# rpi2_relay2.net
KiCad netlist of a schematic drawn in EAGLE
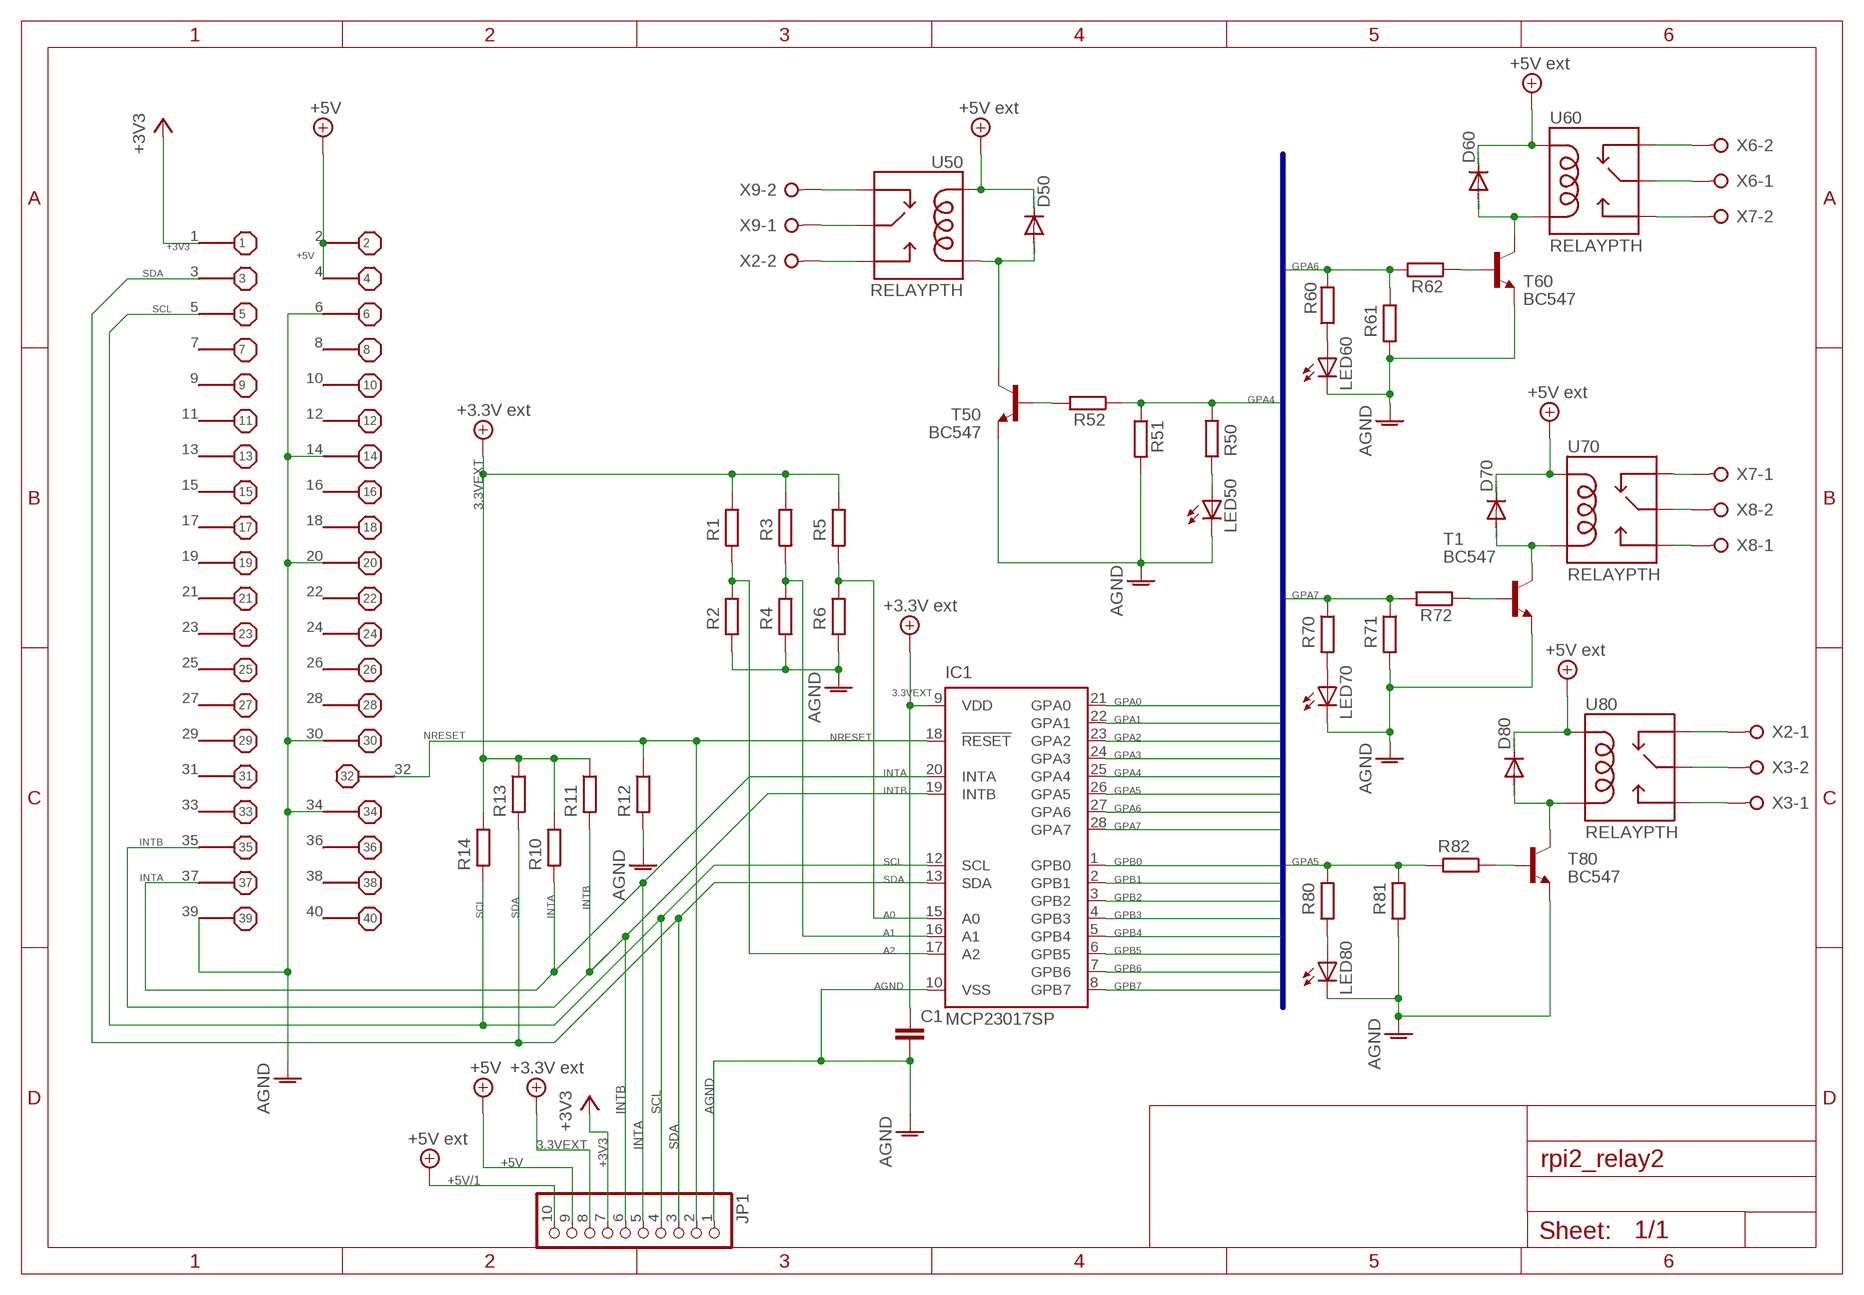
[diagram p0: schematic, sheet 1]

(export (version "E")
  (design (tool "Eeschema 10.0.6"))
  (components
    (comp (ref "C1")
      (value "C-EUC1210")
      (footprint "eagle-import:C1210")
      (libsource (lib "eagle-import") (part "C-EUC1210"))
    )
    (comp (ref "D50")
      (value "1N4148DO35-7")
      (footprint "eagle-import:DO35-7")
      (libsource (lib "eagle-import") (part "1N4148DO35-7"))
    )
    (comp (ref "D60")
      (value "1N4148DO35-7")
      (footprint "eagle-import:DO35-7")
      (libsource (lib "eagle-import") (part "1N4148DO35-7"))
    )
    (comp (ref "D70")
      (value "1N4148DO35-7")
      (footprint "eagle-import:DO35-7")
      (libsource (lib "eagle-import") (part "1N4148DO35-7"))
    )
    (comp (ref "D80")
      (value "1N4148DO35-7")
      (footprint "eagle-import:DO35-7")
      (libsource (lib "eagle-import") (part "1N4148DO35-7"))
    )
    (comp (ref "IC1")
      (value "MCP23017SP")
      (footprint "eagle-import:DIL28-3")
      (fields (field (name "MF") "MICROCHIP") (field (name "MPN") "MCP23017-E/SP"))
      (libsource (lib "eagle-import") (part "MCP23017SP"))
    )
    (comp (ref "JP1")
      (value "PINHD-1X10")
      (footprint "eagle-import:1X10")
      (libsource (lib "eagle-import") (part "PINHD-1X10"))
    )
    (comp (ref "LED50")
      (value "LEDCHIP-LED0805")
      (footprint "eagle-import:CHIP-LED0805")
      (libsource (lib "eagle-import") (part "LEDCHIP-LED0805"))
    )
    (comp (ref "LED60")
      (value "LEDCHIP-LED0805")
      (footprint "eagle-import:CHIP-LED0805")
      (libsource (lib "eagle-import") (part "LEDCHIP-LED0805"))
    )
    (comp (ref "LED70")
      (value "LEDCHIP-LED0805")
      (footprint "eagle-import:CHIP-LED0805")
      (libsource (lib "eagle-import") (part "LEDCHIP-LED0805"))
    )
    (comp (ref "LED80")
      (value "LEDCHIP-LED0805")
      (footprint "eagle-import:CHIP-LED0805")
      (libsource (lib "eagle-import") (part "LEDCHIP-LED0805"))
    )
    (comp (ref "R1")
      (value "R-EU_R0805")
      (footprint "eagle-import:R0805")
      (libsource (lib "eagle-import") (part "R-EU_R0805"))
    )
    (comp (ref "R2")
      (value "R-EU_R0805")
      (footprint "eagle-import:R0805")
      (libsource (lib "eagle-import") (part "R-EU_R0805"))
    )
    (comp (ref "R3")
      (value "R-EU_R0805")
      (footprint "eagle-import:R0805")
      (libsource (lib "eagle-import") (part "R-EU_R0805"))
    )
    (comp (ref "R4")
      (value "R-EU_R0805")
      (footprint "eagle-import:R0805")
      (libsource (lib "eagle-import") (part "R-EU_R0805"))
    )
    (comp (ref "R5")
      (value "R-EU_R0805")
      (footprint "eagle-import:R0805")
      (libsource (lib "eagle-import") (part "R-EU_R0805"))
    )
    (comp (ref "R6")
      (value "R-EU_R0805")
      (footprint "eagle-import:R0805")
      (libsource (lib "eagle-import") (part "R-EU_R0805"))
    )
    (comp (ref "R10")
      (value "R-EU_R0805")
      (footprint "eagle-import:R0805")
      (libsource (lib "eagle-import") (part "R-EU_R0805"))
    )
    (comp (ref "R11")
      (value "R-EU_R0805")
      (footprint "eagle-import:R0805")
      (libsource (lib "eagle-import") (part "R-EU_R0805"))
    )
    (comp (ref "R12")
      (value "R-EU_R0805")
      (footprint "eagle-import:R0805")
      (libsource (lib "eagle-import") (part "R-EU_R0805"))
    )
    (comp (ref "R13")
      (value "R-EU_R0805")
      (footprint "eagle-import:R0805")
      (libsource (lib "eagle-import") (part "R-EU_R0805"))
    )
    (comp (ref "R14")
      (value "R-EU_R0805")
      (footprint "eagle-import:R0805")
      (libsource (lib "eagle-import") (part "R-EU_R0805"))
    )
    (comp (ref "R50")
      (value "R-EU_R0805")
      (footprint "eagle-import:R0805")
      (libsource (lib "eagle-import") (part "R-EU_R0805"))
    )
    (comp (ref "R51")
      (value "R-EU_R0805")
      (footprint "eagle-import:R0805")
      (libsource (lib "eagle-import") (part "R-EU_R0805"))
    )
    (comp (ref "R52")
      (value "R-EU_R0805")
      (footprint "eagle-import:R0805")
      (libsource (lib "eagle-import") (part "R-EU_R0805"))
    )
    (comp (ref "R60")
      (value "R-EU_R0805")
      (footprint "eagle-import:R0805")
      (libsource (lib "eagle-import") (part "R-EU_R0805"))
    )
    (comp (ref "R61")
      (value "R-EU_R0805")
      (footprint "eagle-import:R0805")
      (libsource (lib "eagle-import") (part "R-EU_R0805"))
    )
    (comp (ref "R62")
      (value "R-EU_R0805")
      (footprint "eagle-import:R0805")
      (libsource (lib "eagle-import") (part "R-EU_R0805"))
    )
    (comp (ref "R70")
      (value "R-EU_R0805")
      (footprint "eagle-import:R0805")
      (libsource (lib "eagle-import") (part "R-EU_R0805"))
    )
    (comp (ref "R71")
      (value "R-EU_R0805")
      (footprint "eagle-import:R0805")
      (libsource (lib "eagle-import") (part "R-EU_R0805"))
    )
    (comp (ref "R72")
      (value "R-EU_R0805")
      (footprint "eagle-import:R0805")
      (libsource (lib "eagle-import") (part "R-EU_R0805"))
    )
    (comp (ref "R80")
      (value "R-EU_R0805")
      (footprint "eagle-import:R0805")
      (libsource (lib "eagle-import") (part "R-EU_R0805"))
    )
    (comp (ref "R81")
      (value "R-EU_R0805")
      (footprint "eagle-import:R0805")
      (libsource (lib "eagle-import") (part "R-EU_R0805"))
    )
    (comp (ref "R82")
      (value "R-EU_R0805")
      (footprint "eagle-import:R0805")
      (libsource (lib "eagle-import") (part "R-EU_R0805"))
    )
    (comp (ref "T1")
      (value "BC547")
      (footprint "eagle-import:TO92")
      (libsource (lib "eagle-import") (part "BC547"))
    )
    (comp (ref "T50")
      (value "BC547")
      (footprint "eagle-import:TO92")
      (libsource (lib "eagle-import") (part "BC547"))
    )
    (comp (ref "T60")
      (value "BC547")
      (footprint "eagle-import:TO92")
      (libsource (lib "eagle-import") (part "BC547"))
    )
    (comp (ref "T80")
      (value "BC547")
      (footprint "eagle-import:TO92")
      (libsource (lib "eagle-import") (part "BC547"))
    )
    (comp (ref "U50")
      (value "RELAYPTH")
      (footprint "eagle-import:SRD-05VDC-SL-C")
      (libsource (lib "eagle-import") (part "RELAYPTH"))
    )
    (comp (ref "U60")
      (value "RELAYPTH")
      (footprint "eagle-import:SRD-05VDC-SL-C")
      (libsource (lib "eagle-import") (part "RELAYPTH"))
    )
    (comp (ref "U70")
      (value "RELAYPTH")
      (footprint "eagle-import:SRD-05VDC-SL-C")
      (libsource (lib "eagle-import") (part "RELAYPTH"))
    )
    (comp (ref "U80")
      (value "RELAYPTH")
      (footprint "eagle-import:SRD-05VDC-SL-C")
      (libsource (lib "eagle-import") (part "RELAYPTH"))
    )
    (comp (ref "X1")
      (value "B+_GPIO")
      (footprint "eagle-import:B+_GPIO")
      (libsource (lib "eagle-import") (part "B+_GPIO"))
    )
    (comp (ref "X2")
      (value "W237-02P")
      (footprint "eagle-import:W237-132")
      (libsource (lib "eagle-import") (part "W237-02P"))
    )
    (comp (ref "X3")
      (value "W237-02P")
      (footprint "eagle-import:W237-132")
      (libsource (lib "eagle-import") (part "W237-02P"))
    )
    (comp (ref "X6")
      (value "W237-02P")
      (footprint "eagle-import:W237-132")
      (libsource (lib "eagle-import") (part "W237-02P"))
    )
    (comp (ref "X7")
      (value "W237-02P")
      (footprint "eagle-import:W237-132")
      (libsource (lib "eagle-import") (part "W237-02P"))
    )
    (comp (ref "X8")
      (value "W237-02P")
      (footprint "eagle-import:W237-132")
      (libsource (lib "eagle-import") (part "W237-02P"))
    )
    (comp (ref "X9")
      (value "W237-02P")
      (footprint "eagle-import:W237-132")
      (libsource (lib "eagle-import") (part "W237-02P"))
    )
  )
  (nets
    (net (code "1") (name "+3.3V ext") (class "Default")
      (node (ref "C1") (pin "1") (pinfunction "1_1") (pintype "passive"))
      (node (ref "IC1") (pin "9") (pinfunction "VDD_9") (pintype "power_in"))
      (node (ref "JP1") (pin "8") (pinfunction "8_8") (pintype "passive"))
      (node (ref "R1") (pin "1") (pinfunction "1_1") (pintype "passive"))
      (node (ref "R10") (pin "1") (pinfunction "1_1") (pintype "passive"))
      (node (ref "R11") (pin "1") (pinfunction "1_1") (pintype "passive"))
      (node (ref "R13") (pin "1") (pinfunction "1_1") (pintype "passive"))
      (node (ref "R14") (pin "1") (pinfunction "1_1") (pintype "passive"))
      (node (ref "R3") (pin "1") (pinfunction "1_1") (pintype "passive"))
      (node (ref "R5") (pin "1") (pinfunction "1_1") (pintype "passive"))
    )
    (net (code "2") (name "+3V3") (class "Default")
      (node (ref "JP1") (pin "7") (pinfunction "7_7") (pintype "passive"))
      (node (ref "X1") (pin "1") (pinfunction "P$1_1") (pintype "bidirectional"))
    )
    (net (code "3") (name "+5V") (class "Default")
      (node (ref "JP1") (pin "9") (pinfunction "9_9") (pintype "passive"))
      (node (ref "X1") (pin "2") (pinfunction "P$1_2") (pintype "bidirectional"))
      (node (ref "X1") (pin "4") (pinfunction "P$1_4") (pintype "bidirectional"))
    )
    (net (code "4") (name "+5V ext") (class "Default")
      (node (ref "D50") (pin "C") (pinfunction "C_C") (pintype "passive"))
      (node (ref "D60") (pin "C") (pinfunction "C_C") (pintype "passive"))
      (node (ref "D70") (pin "C") (pinfunction "C_C") (pintype "passive"))
      (node (ref "D80") (pin "C") (pinfunction "C_C") (pintype "passive"))
      (node (ref "JP1") (pin "10") (pinfunction "10_10") (pintype "passive"))
      (node (ref "U50") (pin "COIL1") (pinfunction "COIL1_COIL1") (pintype "bidirectional"))
      (node (ref "U60") (pin "COIL1") (pinfunction "COIL1_COIL1") (pintype "bidirectional"))
      (node (ref "U70") (pin "COIL1") (pinfunction "COIL1_COIL1") (pintype "bidirectional"))
      (node (ref "U80") (pin "COIL1") (pinfunction "COIL1_COIL1") (pintype "bidirectional"))
    )
    (net (code "5") (name "/A0") (class "Default")
      (node (ref "IC1") (pin "15") (pinfunction "A0_15") (pintype "input"))
      (node (ref "R5") (pin "2") (pinfunction "2_2") (pintype "passive"))
      (node (ref "R6") (pin "1") (pinfunction "1_1") (pintype "passive"))
    )
    (net (code "6") (name "/A1") (class "Default")
      (node (ref "IC1") (pin "16") (pinfunction "A1_16") (pintype "input"))
      (node (ref "R3") (pin "2") (pinfunction "2_2") (pintype "passive"))
      (node (ref "R4") (pin "1") (pinfunction "1_1") (pintype "passive"))
    )
    (net (code "7") (name "/A2") (class "Default")
      (node (ref "IC1") (pin "17") (pinfunction "A2_17") (pintype "input"))
      (node (ref "R1") (pin "2") (pinfunction "2_2") (pintype "passive"))
      (node (ref "R2") (pin "1") (pinfunction "1_1") (pintype "passive"))
    )
    (net (code "8") (name "/GPA0") (class "Default")
      (node (ref "IC1") (pin "21") (pinfunction "GPA0_21") (pintype "bidirectional"))
    )
    (net (code "9") (name "/GPA1") (class "Default")
      (node (ref "IC1") (pin "22") (pinfunction "GPA1_22") (pintype "bidirectional"))
    )
    (net (code "10") (name "/GPA2") (class "Default")
      (node (ref "IC1") (pin "23") (pinfunction "GPA2_23") (pintype "bidirectional"))
    )
    (net (code "11") (name "/GPA3") (class "Default")
      (node (ref "IC1") (pin "24") (pinfunction "GPA3_24") (pintype "bidirectional"))
    )
    (net (code "12") (name "/GPA4") (class "Default")
      (node (ref "IC1") (pin "25") (pinfunction "GPA4_25") (pintype "bidirectional"))
      (node (ref "R50") (pin "2") (pinfunction "2_2") (pintype "passive"))
      (node (ref "R51") (pin "1") (pinfunction "1_1") (pintype "passive"))
      (node (ref "R52") (pin "1") (pinfunction "1_1") (pintype "passive"))
    )
    (net (code "13") (name "/GPA5") (class "Default")
      (node (ref "IC1") (pin "26") (pinfunction "GPA5_26") (pintype "bidirectional"))
      (node (ref "R80") (pin "1") (pinfunction "1_1") (pintype "passive"))
      (node (ref "R81") (pin "1") (pinfunction "1_1") (pintype "passive"))
      (node (ref "R82") (pin "2") (pinfunction "2_2") (pintype "passive"))
    )
    (net (code "14") (name "/GPA6") (class "Default")
      (node (ref "IC1") (pin "27") (pinfunction "GPA6_27") (pintype "bidirectional"))
      (node (ref "R60") (pin "2") (pinfunction "2_2") (pintype "passive"))
      (node (ref "R61") (pin "1") (pinfunction "1_1") (pintype "passive"))
      (node (ref "R62") (pin "2") (pinfunction "2_2") (pintype "passive"))
    )
    (net (code "15") (name "/GPA7") (class "Default")
      (node (ref "IC1") (pin "28") (pinfunction "GPA7_28") (pintype "bidirectional"))
      (node (ref "R70") (pin "1") (pinfunction "1_1") (pintype "passive"))
      (node (ref "R71") (pin "1") (pinfunction "1_1") (pintype "passive"))
      (node (ref "R72") (pin "2") (pinfunction "2_2") (pintype "passive"))
    )
    (net (code "16") (name "/GPB0") (class "Default")
      (node (ref "IC1") (pin "1") (pinfunction "GPB0_1") (pintype "bidirectional"))
    )
    (net (code "17") (name "/GPB1") (class "Default")
      (node (ref "IC1") (pin "2") (pinfunction "GPB1_2") (pintype "bidirectional"))
    )
    (net (code "18") (name "/GPB2") (class "Default")
      (node (ref "IC1") (pin "3") (pinfunction "GPB2_3") (pintype "bidirectional"))
    )
    (net (code "19") (name "/GPB3") (class "Default")
      (node (ref "IC1") (pin "4") (pinfunction "GPB3_4") (pintype "bidirectional"))
    )
    (net (code "20") (name "/GPB4") (class "Default")
      (node (ref "IC1") (pin "5") (pinfunction "GPB4_5") (pintype "bidirectional"))
    )
    (net (code "21") (name "/GPB5") (class "Default")
      (node (ref "IC1") (pin "6") (pinfunction "GPB5_6") (pintype "bidirectional"))
    )
    (net (code "22") (name "/GPB6") (class "Default")
      (node (ref "IC1") (pin "7") (pinfunction "GPB6_7") (pintype "bidirectional"))
    )
    (net (code "23") (name "/GPB7") (class "Default")
      (node (ref "IC1") (pin "8") (pinfunction "GPB7_8") (pintype "bidirectional"))
    )
    (net (code "24") (name "/INTA") (class "Default")
      (node (ref "IC1") (pin "20") (pinfunction "INTA_20") (pintype "output"))
      (node (ref "JP1") (pin "5") (pinfunction "5_5") (pintype "passive"))
      (node (ref "R10") (pin "2") (pinfunction "2_2") (pintype "passive"))
      (node (ref "X1") (pin "37") (pinfunction "P$1_37") (pintype "bidirectional"))
    )
    (net (code "25") (name "/INTB") (class "Default")
      (node (ref "IC1") (pin "19") (pinfunction "INTB_19") (pintype "output"))
      (node (ref "JP1") (pin "6") (pinfunction "6_6") (pintype "passive"))
      (node (ref "R11") (pin "2") (pinfunction "2_2") (pintype "passive"))
      (node (ref "X1") (pin "35") (pinfunction "P$1_35") (pintype "bidirectional"))
    )
    (net (code "26") (name "/NRESET") (class "Default")
      (node (ref "IC1") (pin "18") (pinfunction "~{RESET}_18") (pintype "input"))
      (node (ref "JP1") (pin "2") (pinfunction "2_2") (pintype "passive"))
      (node (ref "R12") (pin "1") (pinfunction "1_1") (pintype "passive"))
      (node (ref "X1") (pin "32") (pinfunction "P$1_32") (pintype "bidirectional"))
    )
    (net (code "27") (name "/SCL") (class "Default")
      (node (ref "IC1") (pin "12") (pinfunction "SCL_12") (pintype "input"))
      (node (ref "JP1") (pin "4") (pinfunction "4_4") (pintype "passive"))
      (node (ref "R14") (pin "2") (pinfunction "2_2") (pintype "passive"))
      (node (ref "X1") (pin "5") (pinfunction "P$1_5") (pintype "bidirectional"))
    )
    (net (code "28") (name "/SDA") (class "Default")
      (node (ref "IC1") (pin "13") (pinfunction "SDA_13") (pintype "bidirectional"))
      (node (ref "JP1") (pin "3") (pinfunction "3_3") (pintype "passive"))
      (node (ref "R13") (pin "2") (pinfunction "2_2") (pintype "passive"))
      (node (ref "X1") (pin "3") (pinfunction "P$1_3") (pintype "bidirectional"))
    )
    (net (code "29") (name "AGND") (class "Default")
      (node (ref "C1") (pin "2") (pinfunction "2_2") (pintype "passive"))
      (node (ref "IC1") (pin "10") (pinfunction "VSS_10") (pintype "power_in"))
      (node (ref "JP1") (pin "1") (pinfunction "1_1") (pintype "passive"))
      (node (ref "LED50") (pin "C") (pinfunction "C_C") (pintype "passive"))
      (node (ref "LED60") (pin "C") (pinfunction "C_C") (pintype "passive"))
      (node (ref "LED70") (pin "C") (pinfunction "C_C") (pintype "passive"))
      (node (ref "LED80") (pin "C") (pinfunction "C_C") (pintype "passive"))
      (node (ref "R12") (pin "2") (pinfunction "2_2") (pintype "passive"))
      (node (ref "R2") (pin "2") (pinfunction "2_2") (pintype "passive"))
      (node (ref "R4") (pin "2") (pinfunction "2_2") (pintype "passive"))
      (node (ref "R51") (pin "2") (pinfunction "2_2") (pintype "passive"))
      (node (ref "R6") (pin "2") (pinfunction "2_2") (pintype "passive"))
      (node (ref "R61") (pin "2") (pinfunction "2_2") (pintype "passive"))
      (node (ref "R71") (pin "2") (pinfunction "2_2") (pintype "passive"))
      (node (ref "R81") (pin "2") (pinfunction "2_2") (pintype "passive"))
      (node (ref "T1") (pin "1") (pinfunction "E_1") (pintype "passive"))
      (node (ref "T50") (pin "1") (pinfunction "E_1") (pintype "passive"))
      (node (ref "T60") (pin "1") (pinfunction "E_1") (pintype "passive"))
      (node (ref "T80") (pin "1") (pinfunction "E_1") (pintype "passive"))
      (node (ref "X1") (pin "14") (pinfunction "P$1_14") (pintype "bidirectional"))
      (node (ref "X1") (pin "20") (pinfunction "P$1_20") (pintype "bidirectional"))
      (node (ref "X1") (pin "30") (pinfunction "P$1_30") (pintype "bidirectional"))
      (node (ref "X1") (pin "34") (pinfunction "P$1_34") (pintype "bidirectional"))
      (node (ref "X1") (pin "39") (pinfunction "P$1_39") (pintype "bidirectional"))
      (node (ref "X1") (pin "6") (pinfunction "P$1_6") (pintype "bidirectional"))
    )
    (net (code "30") (name "Net-(LED50-PadA)") (class "Default")
      (node (ref "LED50") (pin "A") (pinfunction "A_A") (pintype "passive"))
      (node (ref "R50") (pin "1") (pinfunction "1_1") (pintype "passive"))
    )
    (net (code "31") (name "Net-(LED60-PadA)") (class "Default")
      (node (ref "LED60") (pin "A") (pinfunction "A_A") (pintype "passive"))
      (node (ref "R60") (pin "1") (pinfunction "1_1") (pintype "passive"))
    )
    (net (code "32") (name "Net-(LED70-PadA)") (class "Default")
      (node (ref "LED70") (pin "A") (pinfunction "A_A") (pintype "passive"))
      (node (ref "R70") (pin "2") (pinfunction "2_2") (pintype "passive"))
    )
    (net (code "33") (name "Net-(LED80-PadA)") (class "Default")
      (node (ref "LED80") (pin "A") (pinfunction "A_A") (pintype "passive"))
      (node (ref "R80") (pin "2") (pinfunction "2_2") (pintype "passive"))
    )
    (net (code "34") (name "Net-(T1-B)") (class "Default")
      (node (ref "R72") (pin "1") (pinfunction "1_1") (pintype "passive"))
      (node (ref "T1") (pin "2") (pinfunction "B_2") (pintype "passive"))
    )
    (net (code "35") (name "Net-(T1-C)") (class "Default")
      (node (ref "D70") (pin "A") (pinfunction "A_A") (pintype "passive"))
      (node (ref "T1") (pin "3") (pinfunction "C_3") (pintype "passive"))
      (node (ref "U70") (pin "COIL0") (pinfunction "COIL0_COIL0") (pintype "bidirectional"))
    )
    (net (code "36") (name "Net-(T50-B)") (class "Default")
      (node (ref "R52") (pin "2") (pinfunction "2_2") (pintype "passive"))
      (node (ref "T50") (pin "2") (pinfunction "B_2") (pintype "passive"))
    )
    (net (code "37") (name "Net-(T50-C)") (class "Default")
      (node (ref "D50") (pin "A") (pinfunction "A_A") (pintype "passive"))
      (node (ref "T50") (pin "3") (pinfunction "C_3") (pintype "passive"))
      (node (ref "U50") (pin "COIL0") (pinfunction "COIL0_COIL0") (pintype "bidirectional"))
    )
    (net (code "38") (name "Net-(T60-B)") (class "Default")
      (node (ref "R62") (pin "1") (pinfunction "1_1") (pintype "passive"))
      (node (ref "T60") (pin "2") (pinfunction "B_2") (pintype "passive"))
    )
    (net (code "39") (name "Net-(T60-C)") (class "Default")
      (node (ref "D60") (pin "A") (pinfunction "A_A") (pintype "passive"))
      (node (ref "T60") (pin "3") (pinfunction "C_3") (pintype "passive"))
      (node (ref "U60") (pin "COIL0") (pinfunction "COIL0_COIL0") (pintype "bidirectional"))
    )
    (net (code "40") (name "Net-(T80-B)") (class "Default")
      (node (ref "R82") (pin "1") (pinfunction "1_1") (pintype "passive"))
      (node (ref "T80") (pin "2") (pinfunction "B_2") (pintype "passive"))
    )
    (net (code "41") (name "Net-(T80-C)") (class "Default")
      (node (ref "D80") (pin "A") (pinfunction "A_A") (pintype "passive"))
      (node (ref "T80") (pin "3") (pinfunction "C_3") (pintype "passive"))
      (node (ref "U80") (pin "COIL0") (pinfunction "COIL0_COIL0") (pintype "bidirectional"))
    )
    (net (code "42") (name "Net-(U50-SWCLOSE)") (class "Default")
      (node (ref "U50") (pin "SWCLOSED") (pinfunction "SWCLOSE_SWCLOSED") (pintype "bidirectional"))
      (node (ref "X9") (pin "2") (pinfunction "KL_2") (pintype "passive"))
    )
    (net (code "43") (name "Net-(U60-SWCLOSE)") (class "Default")
      (node (ref "U60") (pin "SWCLOSED") (pinfunction "SWCLOSE_SWCLOSED") (pintype "bidirectional"))
      (node (ref "X6") (pin "2") (pinfunction "KL_2") (pintype "passive"))
    )
    (net (code "44") (name "Net-(U70-SWCLOSE)") (class "Default")
      (node (ref "U70") (pin "SWCLOSED") (pinfunction "SWCLOSE_SWCLOSED") (pintype "bidirectional"))
      (node (ref "X7") (pin "1") (pinfunction "KL_1") (pintype "passive"))
    )
    (net (code "45") (name "Net-(U80-SWCLOSE)") (class "Default")
      (node (ref "U80") (pin "SWCLOSED") (pinfunction "SWCLOSE_SWCLOSED") (pintype "bidirectional"))
      (node (ref "X2") (pin "1") (pinfunction "KL_1") (pintype "passive"))
    )
    (net (code "46") (name "Net-(X2B-KL)") (class "Default")
      (node (ref "U50") (pin "SWOPEN") (pinfunction "SWOPEN_SWOPEN") (pintype "bidirectional"))
      (node (ref "X2") (pin "2") (pinfunction "KL_2") (pintype "passive"))
    )
    (net (code "47") (name "Net-(X3A-KL)") (class "Default")
      (node (ref "U80") (pin "SWOPEN") (pinfunction "SWOPEN_SWOPEN") (pintype "bidirectional"))
      (node (ref "X3") (pin "1") (pinfunction "KL_1") (pintype "passive"))
    )
    (net (code "48") (name "Net-(X3B-KL)") (class "Default")
      (node (ref "U80") (pin "SWCOMMON") (pinfunction "SWCOMMON_SWCOMMON") (pintype "bidirectional"))
      (node (ref "X3") (pin "2") (pinfunction "KL_2") (pintype "passive"))
    )
    (net (code "49") (name "Net-(X6A-KL)") (class "Default")
      (node (ref "U60") (pin "SWCOMMON") (pinfunction "SWCOMMON_SWCOMMON") (pintype "bidirectional"))
      (node (ref "X6") (pin "1") (pinfunction "KL_1") (pintype "passive"))
    )
    (net (code "50") (name "Net-(X7B-KL)") (class "Default")
      (node (ref "U60") (pin "SWOPEN") (pinfunction "SWOPEN_SWOPEN") (pintype "bidirectional"))
      (node (ref "X7") (pin "2") (pinfunction "KL_2") (pintype "passive"))
    )
    (net (code "51") (name "Net-(X8A-KL)") (class "Default")
      (node (ref "U70") (pin "SWOPEN") (pinfunction "SWOPEN_SWOPEN") (pintype "bidirectional"))
      (node (ref "X8") (pin "1") (pinfunction "KL_1") (pintype "passive"))
    )
    (net (code "52") (name "Net-(X8B-KL)") (class "Default")
      (node (ref "U70") (pin "SWCOMMON") (pinfunction "SWCOMMON_SWCOMMON") (pintype "bidirectional"))
      (node (ref "X8") (pin "2") (pinfunction "KL_2") (pintype "passive"))
    )
    (net (code "53") (name "Net-(X9A-KL)") (class "Default")
      (node (ref "U50") (pin "SWCOMMON") (pinfunction "SWCOMMON_SWCOMMON") (pintype "bidirectional"))
      (node (ref "X9") (pin "1") (pinfunction "KL_1") (pintype "passive"))
    )
    (net (code "54") (name "unconnected-(X1AA-P$1-Pad33)") (class "Default")
      (node (ref "X1") (pin "33") (pinfunction "P$1_33") (pintype "bidirectional"))
    )
    (net (code "55") (name "unconnected-(X1AD-P$1-Pad36)") (class "Default")
      (node (ref "X1") (pin "36") (pinfunction "P$1_36") (pintype "bidirectional"))
    )
    (net (code "56") (name "unconnected-(X1AF-P$1-Pad38)") (class "Default")
      (node (ref "X1") (pin "38") (pinfunction "P$1_38") (pintype "bidirectional"))
    )
    (net (code "57") (name "unconnected-(X1AI-P$1-Pad40)") (class "Default")
      (node (ref "X1") (pin "40") (pinfunction "P$1_40") (pintype "bidirectional"))
    )
    (net (code "58") (name "unconnected-(X1AL-P$1-Pad7)") (class "Default")
      (node (ref "X1") (pin "7") (pinfunction "P$1_7") (pintype "bidirectional"))
    )
    (net (code "59") (name "unconnected-(X1AM-P$1-Pad8)") (class "Default")
      (node (ref "X1") (pin "8") (pinfunction "P$1_8") (pintype "bidirectional"))
    )
    (net (code "60") (name "unconnected-(X1AN-P$1-Pad9)") (class "Default")
      (node (ref "X1") (pin "9") (pinfunction "P$1_9") (pintype "bidirectional"))
    )
    (net (code "61") (name "unconnected-(X1B-P$1-Pad10)") (class "Default")
      (node (ref "X1") (pin "10") (pinfunction "P$1_10") (pintype "bidirectional"))
    )
    (net (code "62") (name "unconnected-(X1C-P$1-Pad11)") (class "Default")
      (node (ref "X1") (pin "11") (pinfunction "P$1_11") (pintype "bidirectional"))
    )
    (net (code "63") (name "unconnected-(X1D-P$1-Pad12)") (class "Default")
      (node (ref "X1") (pin "12") (pinfunction "P$1_12") (pintype "bidirectional"))
    )
    (net (code "64") (name "unconnected-(X1E-P$1-Pad13)") (class "Default")
      (node (ref "X1") (pin "13") (pinfunction "P$1_13") (pintype "bidirectional"))
    )
    (net (code "65") (name "unconnected-(X1G-P$1-Pad15)") (class "Default")
      (node (ref "X1") (pin "15") (pinfunction "P$1_15") (pintype "bidirectional"))
    )
    (net (code "66") (name "unconnected-(X1H-P$1-Pad16)") (class "Default")
      (node (ref "X1") (pin "16") (pinfunction "P$1_16") (pintype "bidirectional"))
    )
    (net (code "67") (name "unconnected-(X1I-P$1-Pad17)") (class "Default")
      (node (ref "X1") (pin "17") (pinfunction "P$1_17") (pintype "bidirectional"))
    )
    (net (code "68") (name "unconnected-(X1J-P$1-Pad18)") (class "Default")
      (node (ref "X1") (pin "18") (pinfunction "P$1_18") (pintype "bidirectional"))
    )
    (net (code "69") (name "unconnected-(X1K-P$1-Pad19)") (class "Default")
      (node (ref "X1") (pin "19") (pinfunction "P$1_19") (pintype "bidirectional"))
    )
    (net (code "70") (name "unconnected-(X1N-P$1-Pad21)") (class "Default")
      (node (ref "X1") (pin "21") (pinfunction "P$1_21") (pintype "bidirectional"))
    )
    (net (code "71") (name "unconnected-(X1O-P$1-Pad22)") (class "Default")
      (node (ref "X1") (pin "22") (pinfunction "P$1_22") (pintype "bidirectional"))
    )
    (net (code "72") (name "unconnected-(X1P-P$1-Pad23)") (class "Default")
      (node (ref "X1") (pin "23") (pinfunction "P$1_23") (pintype "bidirectional"))
    )
    (net (code "73") (name "unconnected-(X1Q-P$1-Pad24)") (class "Default")
      (node (ref "X1") (pin "24") (pinfunction "P$1_24") (pintype "bidirectional"))
    )
    (net (code "74") (name "unconnected-(X1R-P$1-Pad25)") (class "Default")
      (node (ref "X1") (pin "25") (pinfunction "P$1_25") (pintype "bidirectional"))
    )
    (net (code "75") (name "unconnected-(X1S-P$1-Pad26)") (class "Default")
      (node (ref "X1") (pin "26") (pinfunction "P$1_26") (pintype "bidirectional"))
    )
    (net (code "76") (name "unconnected-(X1T-P$1-Pad27)") (class "Default")
      (node (ref "X1") (pin "27") (pinfunction "P$1_27") (pintype "bidirectional"))
    )
    (net (code "77") (name "unconnected-(X1U-P$1-Pad28)") (class "Default")
      (node (ref "X1") (pin "28") (pinfunction "P$1_28") (pintype "bidirectional"))
    )
    (net (code "78") (name "unconnected-(X1V-P$1-Pad29)") (class "Default")
      (node (ref "X1") (pin "29") (pinfunction "P$1_29") (pintype "bidirectional"))
    )
    (net (code "79") (name "unconnected-(X1Y-P$1-Pad31)") (class "Default")
      (node (ref "X1") (pin "31") (pinfunction "P$1_31") (pintype "bidirectional"))
    )
  )
)
